# dsau-motherboard-top.net
KiCad netlist of a schematic drawn in Altium Designer
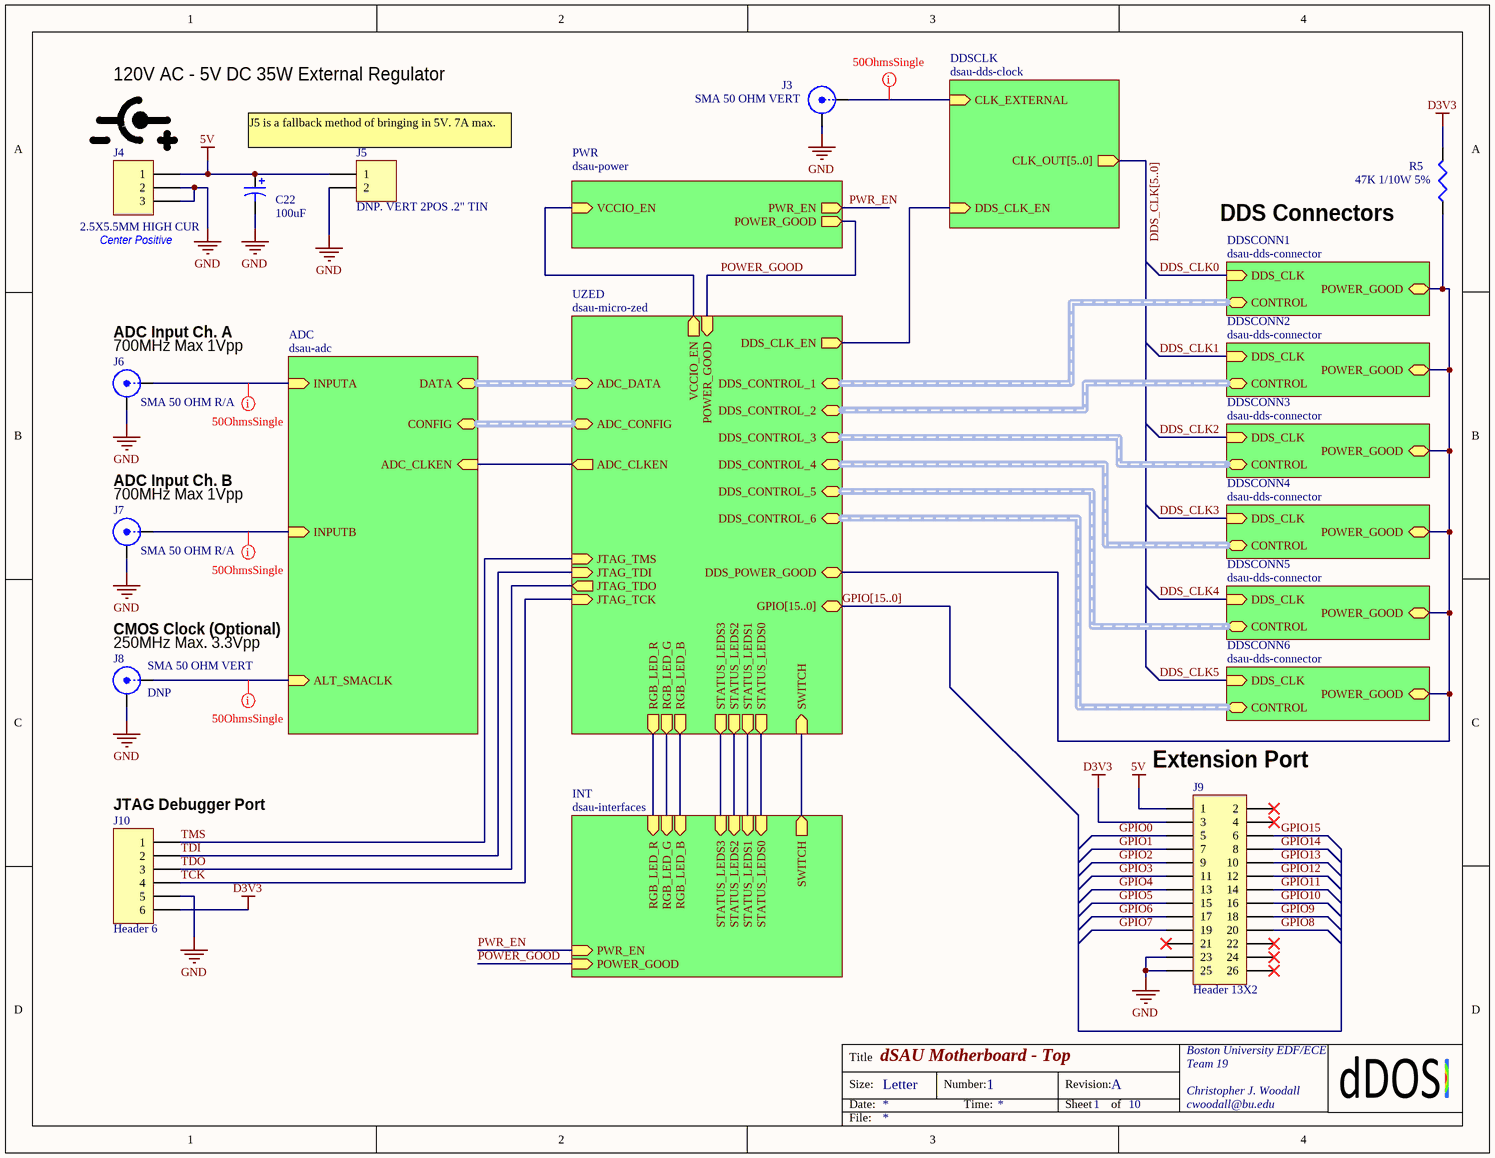
[diagram p0: dsau-motherboard-top.SchDoc]

(export (version "E")
  (design (tool "Eeschema 10.0.6"))
  (components
    (comp (ref "C22")
      (value "100uF")
      (footprint "CAPPOL3216")
      (description "Polarized Capacitor (Surface Mount)")
      (fields
        (field (name "MANUFACTURER") "Vishay Sprague")
        (field (name "MANUFACTURER PART NUMBER") "TL8A0107M010C")
        (field (name "PUBLISHER") "Altium Limited")
      )
      (libsource (lib "Miscellaneous Devices") (part "Cap Pol3"))
    )
    (comp (ref "J3")
      (value "SMA 50 OHM VERT")
      (footprint "MOLEX_SMBVERT_731000207")
      (description "SMB Straight Connector")
      (fields
        (field (name "MANUFACTURER") "Molex Inc")
        (field (name "MANUFACTURER PART NUMBER") "0733910060")
        (field (name "PUBLISHER") "Altium Limited")
      )
      (libsource (lib "Miscellaneous Connectors") (part "SMB"))
    )
    (comp (ref "J4")
      (value "2.5X5.5MM HIGH CUR")
      (footprint "PJ-002BH")
      (description "Header, 3-Pin")
      (fields
        (field (name "MANUFACTURER") "CUI Inc")
        (field (name "MANUFACTURER PART NUMBER") "PJ-002BH")
        (field (name "PUBLISHER") "Altium Limited")
      )
      (libsource (lib "Miscellaneous Connectors") (part "Header 3"))
    )
    (comp (ref "J5")
      (value "DNP. VERT 2POS .2\" TIN")
      (footprint "MOLEX_2POS_200mil_0010085021")
      (description "Header, 2-Pin")
      (fields
        (field (name "MANUFACTURER") "Molex Inc")
        (field (name "MANUFACTURER PART NUMBER") "0010085021")
        (field (name "PUBLISHER") "Altium Limited")
      )
      (libsource (lib "Miscellaneous Connectors") (part "Header 2"))
    )
    (comp (ref "J6")
      (value "SMA 50 OHM R/A")
      (footprint "MOLEX_SMBRA_731000103")
      (description "SMB Straight Connector")
      (fields
        (field (name "MANUFACTURER") "Molex Inc")
        (field (name "MANUFACTURER PART NUMBER") "0733910320")
        (field (name "PUBLISHER") "Altium Limited")
      )
      (libsource (lib "Miscellaneous Connectors") (part "SMB"))
    )
    (comp (ref "J7")
      (value "SMA 50 OHM R/A")
      (footprint "MOLEX_SMBRA_731000103")
      (description "SMB Straight Connector")
      (fields
        (field (name "MANUFACTURER") "Molex Inc")
        (field (name "MANUFACTURER PART NUMBER") "0733910320")
        (field (name "PUBLISHER") "Altium Limited")
      )
      (libsource (lib "Miscellaneous Connectors") (part "SMB"))
    )
    (comp (ref "J8")
      (value "SMA 50 OHM VERT")
      (footprint "MOLEX_SMBVERT_731000207")
      (description "SMB Straight Connector")
      (fields
        (field (name "ALTIUM_VALUE") "DNP")
        (field (name "MANUFACTURER") "Molex Inc")
        (field (name "MANUFACTURER PART NUMBER") "0733910060")
        (field (name "PUBLISHER") "Altium Limited")
      )
      (libsource (lib "Miscellaneous Connectors") (part "SMB"))
    )
    (comp (ref "J9")
      (value "Header 13X2")
      (footprint "HDR2X13")
      (description "Header, 13-Pin, Dual row")
      (fields (field (name "PUBLISHER") "Altium Limited"))
      (libsource (lib "Miscellaneous Connectors") (part "Header 13X2"))
    )
    (comp (ref "J10")
      (value "Header 6")
      (footprint "HDR1X6")
      (description "Header, 6-Pin")
      (fields (field (name "PUBLISHER") "Altium Limited"))
      (libsource (lib "Miscellaneous Connectors") (part "Header 6"))
    )
    (comp (ref "R5")
      (value "47K 1/10W 5%")
      (footprint "RESC1608L")
      (description "Resistor")
      (fields
        (field (name "MANUFACTURER") "Yageo")
        (field (name "MANUFACTURER PART NUMBER") "311-47kGRCT-ND")
        (field (name "PUBLISHER") "Altium Limited")
      )
      (libsource (lib "Miscellaneous Devices") (part "Res3"))
    )
  )
  (nets
    (net (code "4") (name "/ALT_SMACLK") (class "Default")
      (node (ref "J8") (pin "1") (pinfunction "X_1") (pintype "passive"))
    )
    (net (code "5") (name "/CLK_EXTERNAL") (class "Default")
      (node (ref "J3") (pin "1") (pinfunction "X_1") (pintype "passive"))
    )
    (net (code "20") (name "/DDS_POWER_GOOD") (class "Default")
      (node (ref "R5") (pin "1") (pinfunction "1_1") (pintype "passive"))
    )
    (net (code "21") (name "/GPIO0") (class "Default")
      (node (ref "J9") (pin "5") (pinfunction "5_5") (pintype "passive"))
    )
    (net (code "22") (name "/GPIO1") (class "Default")
      (node (ref "J9") (pin "7") (pinfunction "7_7") (pintype "passive"))
    )
    (net (code "23") (name "/GPIO2") (class "Default")
      (node (ref "J9") (pin "9") (pinfunction "9_9") (pintype "passive"))
    )
    (net (code "24") (name "/GPIO3") (class "Default")
      (node (ref "J9") (pin "11") (pinfunction "11_11") (pintype "passive"))
    )
    (net (code "25") (name "/GPIO4") (class "Default")
      (node (ref "J9") (pin "13") (pinfunction "13_13") (pintype "passive"))
    )
    (net (code "26") (name "/GPIO5") (class "Default")
      (node (ref "J9") (pin "15") (pinfunction "15_15") (pintype "passive"))
    )
    (net (code "27") (name "/GPIO6") (class "Default")
      (node (ref "J9") (pin "17") (pinfunction "17_17") (pintype "passive"))
    )
    (net (code "28") (name "/GPIO7") (class "Default")
      (node (ref "J9") (pin "19") (pinfunction "19_19") (pintype "passive"))
    )
    (net (code "29") (name "/GPIO8") (class "Default")
      (node (ref "J9") (pin "20") (pinfunction "20_20") (pintype "passive"))
    )
    (net (code "30") (name "/GPIO9") (class "Default")
      (node (ref "J9") (pin "18") (pinfunction "18_18") (pintype "passive"))
    )
    (net (code "31") (name "/GPIO10") (class "Default")
      (node (ref "J9") (pin "16") (pinfunction "16_16") (pintype "passive"))
    )
    (net (code "32") (name "/GPIO11") (class "Default")
      (node (ref "J9") (pin "14") (pinfunction "14_14") (pintype "passive"))
    )
    (net (code "33") (name "/GPIO12") (class "Default")
      (node (ref "J9") (pin "12") (pinfunction "12_12") (pintype "passive"))
    )
    (net (code "34") (name "/GPIO13") (class "Default")
      (node (ref "J9") (pin "10") (pinfunction "10_10") (pintype "passive"))
    )
    (net (code "35") (name "/GPIO14") (class "Default")
      (node (ref "J9") (pin "8") (pinfunction "8_8") (pintype "passive"))
    )
    (net (code "36") (name "/GPIO15") (class "Default")
      (node (ref "J9") (pin "6") (pinfunction "6_6") (pintype "passive"))
    )
    (net (code "38") (name "/INPUTA") (class "Default")
      (node (ref "J6") (pin "1") (pinfunction "X_1") (pintype "passive"))
    )
    (net (code "39") (name "/INPUTB") (class "Default")
      (node (ref "J7") (pin "1") (pinfunction "X_1") (pintype "passive"))
    )
    (net (code "50") (name "/TCK") (class "Default")
      (node (ref "J10") (pin "4") (pinfunction "4_4") (pintype "passive"))
    )
    (net (code "51") (name "/TDI") (class "Default")
      (node (ref "J10") (pin "2") (pinfunction "2_2") (pintype "passive"))
    )
    (net (code "52") (name "/TDO") (class "Default")
      (node (ref "J10") (pin "3") (pinfunction "3_3") (pintype "passive"))
    )
    (net (code "53") (name "/TMS") (class "Default")
      (node (ref "J10") (pin "1") (pinfunction "1_1") (pintype "passive"))
    )
    (net (code "55") (name "5V") (class "Default")
      (node (ref "C22") (pin "1") (pinfunction "1_1") (pintype "passive"))
      (node (ref "J4") (pin "1") (pinfunction "1_1") (pintype "passive"))
      (node (ref "J5") (pin "1") (pinfunction "1_1") (pintype "passive"))
      (node (ref "J9") (pin "1") (pinfunction "1_1") (pintype "passive"))
    )
    (net (code "56") (name "D3V3") (class "Default")
      (node (ref "J10") (pin "6") (pinfunction "6_6") (pintype "passive"))
      (node (ref "J9") (pin "3") (pinfunction "3_3") (pintype "passive"))
      (node (ref "R5") (pin "2") (pinfunction "2_2") (pintype "passive"))
    )
    (net (code "57") (name "GND") (class "Default")
      (node (ref "C22") (pin "2") (pinfunction "2_2") (pintype "passive"))
      (node (ref "J10") (pin "5") (pinfunction "5_5") (pintype "passive"))
      (node (ref "J3") (pin "2") (pinfunction "Y_2") (pintype "passive"))
      (node (ref "J4") (pin "2") (pinfunction "2_2") (pintype "passive"))
      (node (ref "J4") (pin "3") (pinfunction "3_3") (pintype "passive"))
      (node (ref "J5") (pin "2") (pinfunction "2_2") (pintype "passive"))
      (node (ref "J6") (pin "2") (pinfunction "Y_2") (pintype "passive"))
      (node (ref "J7") (pin "2") (pinfunction "Y_2") (pintype "passive"))
      (node (ref "J8") (pin "2") (pinfunction "Y_2") (pintype "passive"))
      (node (ref "J9") (pin "23") (pinfunction "23_23") (pintype "passive"))
      (node (ref "J9") (pin "25") (pinfunction "25_25") (pintype "passive"))
    )
    (net (code "58") (name "unconnected-(J9-Pad2)") (class "Default")
      (node (ref "J9") (pin "2") (pinfunction "2_2") (pintype "passive+no_connect"))
    )
    (net (code "59") (name "unconnected-(J9-Pad4)") (class "Default")
      (node (ref "J9") (pin "4") (pinfunction "4_4") (pintype "passive+no_connect"))
    )
    (net (code "60") (name "unconnected-(J9-Pad21)") (class "Default")
      (node (ref "J9") (pin "21") (pinfunction "21_21") (pintype "passive+no_connect"))
    )
    (net (code "61") (name "unconnected-(J9-Pad22)") (class "Default")
      (node (ref "J9") (pin "22") (pinfunction "22_22") (pintype "passive+no_connect"))
    )
    (net (code "62") (name "unconnected-(J9-Pad24)") (class "Default")
      (node (ref "J9") (pin "24") (pinfunction "24_24") (pintype "passive+no_connect"))
    )
    (net (code "63") (name "unconnected-(J9-Pad26)") (class "Default")
      (node (ref "J9") (pin "26") (pinfunction "26_26") (pintype "passive+no_connect"))
    )
  )
)
